# SchemaC-mcu.net
KiCad netlist of a schematic drawn in Altium Designer
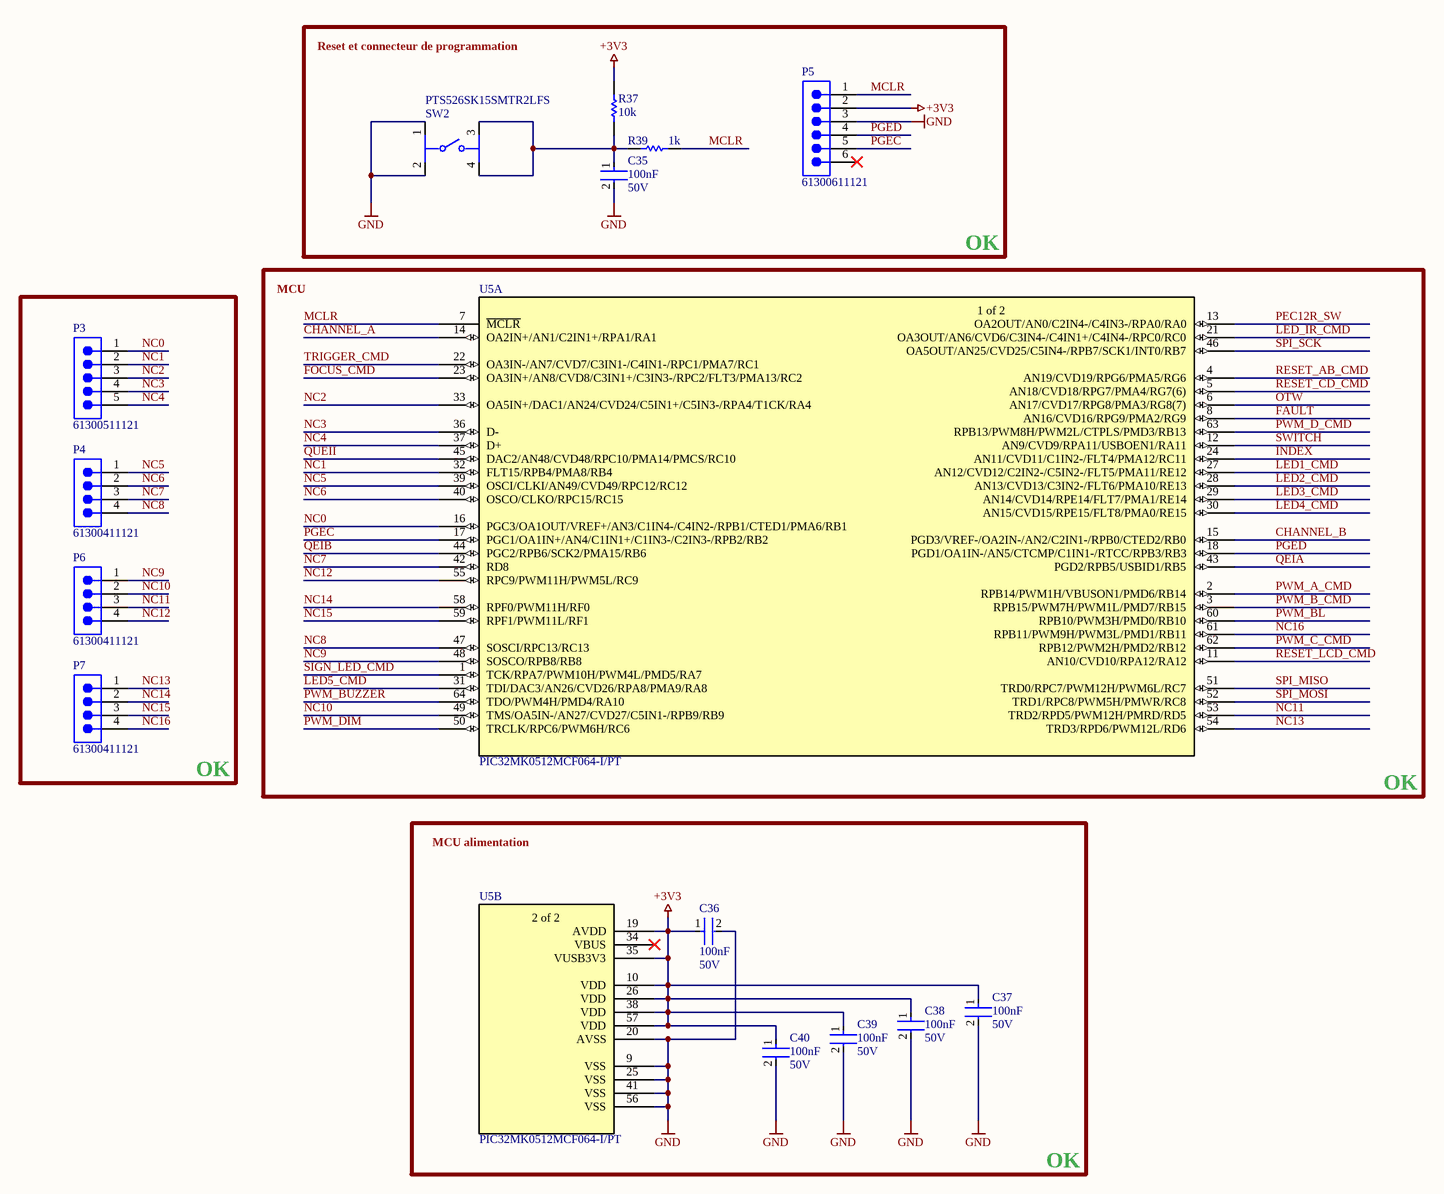
[diagram p0: SchemaC-mcu.SchDoc]

(export (version "E")
  (design (tool "Eeschema 10.0.6"))
  (components
    (comp (ref "C35")
      (value "CL21B104KBCNNNC")
      (footprint "FP-CL21-IPC_C")
      (description "CL21 Series 0805 100nF 50V ±10% Tolerance X7R Multilayer Ceramic Chip Capacitor")
      (fields
        (field (name "TOLERANCE") "10%")
        (field (name "CAPACITANCE") "100nF")
        (field (name "VOLTAGE RATING") "50V")
        (field (name "VOLTAGE") "50V")
      )
      (libsource (lib "Altium Content Vault") (part "b4654b650e69147ec39a6b967a45e02"))
    )
    (comp (ref "C36")
      (value "CL21B104KBCNNNC")
      (footprint "FP-CL21-IPC_C")
      (description "CL21 Series 0805 100nF 50V ±10% Tolerance X7R Multilayer Ceramic Chip Capacitor")
      (fields
        (field (name "TOLERANCE") "10%")
        (field (name "CAPACITANCE") "100nF")
        (field (name "VOLTAGE RATING") "50V")
        (field (name "VOLTAGE") "50V")
      )
      (libsource (lib "Altium Content Vault") (part "b4654b650e69147ec39a6b967a45e02"))
    )
    (comp (ref "C37")
      (value "CL21B104KBCNNNC")
      (footprint "FP-CL21-IPC_C")
      (description "CL21 Series 0805 100nF 50V ±10% Tolerance X7R Multilayer Ceramic Chip Capacitor")
      (fields
        (field (name "TOLERANCE") "10%")
        (field (name "CAPACITANCE") "100nF")
        (field (name "VOLTAGE RATING") "50V")
        (field (name "VOLTAGE") "50V")
      )
      (libsource (lib "Altium Content Vault") (part "b4654b650e69147ec39a6b967a45e02"))
    )
    (comp (ref "C38")
      (value "CL21B104KBCNNNC")
      (footprint "FP-CL21-IPC_C")
      (description "CL21 Series 0805 100nF 50V ±10% Tolerance X7R Multilayer Ceramic Chip Capacitor")
      (fields
        (field (name "TOLERANCE") "10%")
        (field (name "CAPACITANCE") "100nF")
        (field (name "VOLTAGE RATING") "50V")
        (field (name "VOLTAGE") "50V")
      )
      (libsource (lib "Altium Content Vault") (part "b4654b650e69147ec39a6b967a45e02"))
    )
    (comp (ref "C39")
      (value "CL21B104KBCNNNC")
      (footprint "FP-CL21-IPC_C")
      (description "CL21 Series 0805 100nF 50V ±10% Tolerance X7R Multilayer Ceramic Chip Capacitor")
      (fields
        (field (name "TOLERANCE") "10%")
        (field (name "CAPACITANCE") "100nF")
        (field (name "VOLTAGE RATING") "50V")
        (field (name "VOLTAGE") "50V")
      )
      (libsource (lib "Altium Content Vault") (part "b4654b650e69147ec39a6b967a45e02"))
    )
    (comp (ref "C40")
      (value "CL21B104KBCNNNC")
      (footprint "FP-CL21-IPC_C")
      (description "CL21 Series 0805 100nF 50V ±10% Tolerance X7R Multilayer Ceramic Chip Capacitor")
      (fields
        (field (name "TOLERANCE") "10%")
        (field (name "CAPACITANCE") "100nF")
        (field (name "VOLTAGE RATING") "50V")
        (field (name "VOLTAGE") "50V")
      )
      (libsource (lib "Altium Content Vault") (part "b4654b650e69147ec39a6b967a45e02"))
    )
    (comp (ref "P3")
      (value "61300511121")
      (footprint "61300511121")
      (libsource (lib "Altium Content Vault") (part "Header_Male_1R_05P"))
    )
    (comp (ref "P4")
      (value "61300411121")
      (footprint "61300411121")
      (libsource (lib "Altium Content Vault") (part "Header_Male_1R_04P"))
    )
    (comp (ref "P5")
      (value "61300611121")
      (footprint "61300611121")
      (libsource (lib "Altium Content Vault") (part "Header_Male_1R_06P"))
    )
    (comp (ref "P6")
      (value "61300411121")
      (footprint "61300411121")
      (libsource (lib "Altium Content Vault") (part "Header_Male_1R_04P"))
    )
    (comp (ref "P7")
      (value "61300411121")
      (footprint "61300411121")
      (libsource (lib "Altium Content Vault") (part "Header_Male_1R_04P"))
    )
    (comp (ref "R37")
      (value "RC0805JR-0710KL")
      (footprint "RESC2013X60X35ML10T20")
      (description "Chip Resistor, 10 KOhm, +/- 5%, 0.125 W, -55 to 155 degC, 0805 (2012 Metric), RoHS, Tape and Reel")
      (fields (field (name "MANUFACTURER") "Yageo") (field (name "RESISTANCE") "10k"))
      (libsource (lib "Altium Content Vault") (part "RES-2"))
    )
    (comp (ref "R39")
      (value "RC0805FR-071KL")
      (footprint "RESC2013X60X35ML10T20")
      (description "Chip Resistor, 1 KOhm, +/- 1%, 125 mW, -55 to 155 degC, 0805 (2012 Metric), RoHS, Tape and Reel")
      (fields
        (field (name "RESISTANCE") "1k")
        (field (name "TOLERANCE") "1%")
        (field (name "MANUFACTURER") "Yageo")
      )
      (libsource (lib "Altium Content Vault") (part "RES-2"))
    )
    (comp (ref "SW2")
      (value "PTS526SK15SMTR2LFS")
      (footprint "FP-PTS526SK15SMTR2LFS-MFG")
      (description "TACT 5.2 X 5.2, 1.5 MM H, 260GF,")
      (fields
        (field (name "MANUFACTURER") "C&K")
        (field (name "OCTOPART") "https://octopart.com/pts526+sk15+smtr2+lfs-c%26k+components-100617999")
      )
      (libsource (lib "Altium Content Vault") (part "b8895f3f4cefb76e1819d2863dba89b"))
    )
    (comp (ref "U5")
      (value "PIC32MK0512MCF064-I/PT")
      (footprint "TQFP64_PT_MCH")
      (fields (field (name "COPYRIGHT") "Copyright (C) 2023 Ultra Librarian. All rights reserved."))
      (libsource (lib "SymbLib") (part "PIC32MK0512MCF064-I/PT"))
    )
  )
  (nets
    (net (code "1") (name "+3V3") (class "Default")
      (node (ref "C36") (pin "1") (pinfunction "1_1") (pintype "passive"))
      (node (ref "C37") (pin "1") (pinfunction "1_1") (pintype "passive"))
      (node (ref "C38") (pin "1") (pinfunction "1_1") (pintype "passive"))
      (node (ref "C39") (pin "1") (pinfunction "1_1") (pintype "passive"))
      (node (ref "C40") (pin "1") (pinfunction "1_1") (pintype "passive"))
      (node (ref "P5") (pin "2") (pinfunction "2_2") (pintype "passive"))
      (node (ref "R37") (pin "1") (pinfunction "1_1") (pintype "passive"))
      (node (ref "U5") (pin "10") (pinfunction "VDD_10") (pintype "power_in"))
      (node (ref "U5") (pin "19") (pinfunction "AVDD_19") (pintype "power_in"))
      (node (ref "U5") (pin "26") (pinfunction "VDD_26") (pintype "power_in"))
      (node (ref "U5") (pin "35") (pinfunction "VUSB3V3_35") (pintype "power_in"))
      (node (ref "U5") (pin "38") (pinfunction "VDD_38") (pintype "power_in"))
      (node (ref "U5") (pin "57") (pinfunction "VDD_57") (pintype "power_in"))
    )
    (net (code "2") (name "/CHANNEL_A") (class "Default")
      (node (ref "U5") (pin "14") (pinfunction "OA2IN+/AN1/C2IN1+/RPA1/RA1_14") (pintype "bidirectional"))
    )
    (net (code "3") (name "/CHANNEL_B") (class "Default")
      (node (ref "U5") (pin "15") (pinfunction "PGD3/VREF-/OA2IN-/AN2/C2IN1-/RPB0/CTED2/RB0_15") (pintype "bidirectional"))
    )
    (net (code "4") (name "/FAULT") (class "Default")
      (node (ref "U5") (pin "8") (pinfunction "AN16/CVD16/RPG9/PMA2/RG9_8") (pintype "bidirectional"))
    )
    (net (code "5") (name "/FOCUS_CMD") (class "Default")
      (node (ref "U5") (pin "23") (pinfunction "OA3IN+/AN8/CVD8/C3IN1+/C3IN3-/RPC2/FLT3/PMA13/RC2_23") (pintype "bidirectional"))
    )
    (net (code "6") (name "/INDEX") (class "Default")
      (node (ref "U5") (pin "24") (pinfunction "AN11/CVD11/C1IN2-/FLT4/PMA12/RC11_24") (pintype "bidirectional"))
    )
    (net (code "7") (name "/LED1_CMD") (class "Default")
      (node (ref "U5") (pin "27") (pinfunction "AN12/CVD12/C2IN2-/C5IN2-/FLT5/PMA11/RE12_27") (pintype "bidirectional"))
    )
    (net (code "8") (name "/LED2_CMD") (class "Default")
      (node (ref "U5") (pin "28") (pinfunction "AN13/CVD13/C3IN2-/FLT6/PMA10/RE13_28") (pintype "bidirectional"))
    )
    (net (code "9") (name "/LED3_CMD") (class "Default")
      (node (ref "U5") (pin "29") (pinfunction "AN14/CVD14/RPE14/FLT7/PMA1/RE14_29") (pintype "bidirectional"))
    )
    (net (code "10") (name "/LED4_CMD") (class "Default")
      (node (ref "U5") (pin "30") (pinfunction "AN15/CVD15/RPE15/FLT8/PMA0/RE15_30") (pintype "bidirectional"))
    )
    (net (code "11") (name "/LED5_CMD") (class "Default")
      (node (ref "U5") (pin "31") (pinfunction "TDI/DAC3/AN26/CVD26/RPA8/PMA9/RA8_31") (pintype "bidirectional"))
    )
    (net (code "12") (name "/LED_IR_CMD") (class "Default")
      (node (ref "U5") (pin "21") (pinfunction "OA3OUT/AN6/CVD6/C3IN4-/C4IN1+/C4IN4-/RPC0/RC0_21") (pintype "bidirectional"))
    )
    (net (code "13") (name "/MCLR") (class "Default")
      (node (ref "P5") (pin "1") (pinfunction "1_1") (pintype "passive"))
      (node (ref "R39") (pin "2") (pinfunction "2_2") (pintype "passive"))
      (node (ref "U5") (pin "7") (pinfunction "~{MCLR}_7") (pintype "passive"))
    )
    (net (code "14") (name "/NC0") (class "Default")
      (node (ref "P3") (pin "1") (pinfunction "1_1") (pintype "passive"))
      (node (ref "U5") (pin "16") (pinfunction "PGC3/OA1OUT/VREF+/AN3/C1IN4-/C4IN2-/RPB1/CTED1/PMA6/RB1_16") (pintype "bidirectional"))
    )
    (net (code "15") (name "/NC1") (class "Default")
      (node (ref "P3") (pin "2") (pinfunction "2_2") (pintype "passive"))
      (node (ref "U5") (pin "32") (pinfunction "FLT15/RPB4/PMA8/RB4_32") (pintype "bidirectional"))
    )
    (net (code "16") (name "/NC2") (class "Default")
      (node (ref "P3") (pin "3") (pinfunction "3_3") (pintype "passive"))
      (node (ref "U5") (pin "33") (pinfunction "OA5IN+/DAC1/AN24/CVD24/C5IN1+/C5IN3-/RPA4/T1CK/RA4_33") (pintype "bidirectional"))
    )
    (net (code "17") (name "/NC3") (class "Default")
      (node (ref "P3") (pin "4") (pinfunction "4_4") (pintype "passive"))
      (node (ref "U5") (pin "36") (pinfunction "D-_36") (pintype "bidirectional"))
    )
    (net (code "18") (name "/NC4") (class "Default")
      (node (ref "P3") (pin "5") (pinfunction "5_5") (pintype "passive"))
      (node (ref "U5") (pin "37") (pinfunction "D+_37") (pintype "bidirectional"))
    )
    (net (code "19") (name "/NC5") (class "Default")
      (node (ref "P4") (pin "1") (pinfunction "1_1") (pintype "passive"))
      (node (ref "U5") (pin "39") (pinfunction "OSCI/CLKI/AN49/CVD49/RPC12/RC12_39") (pintype "bidirectional"))
    )
    (net (code "20") (name "/NC6") (class "Default")
      (node (ref "P4") (pin "2") (pinfunction "2_2") (pintype "passive"))
      (node (ref "U5") (pin "40") (pinfunction "OSCO/CLKO/RPC15/RC15_40") (pintype "bidirectional"))
    )
    (net (code "21") (name "/NC7") (class "Default")
      (node (ref "P4") (pin "3") (pinfunction "3_3") (pintype "passive"))
      (node (ref "U5") (pin "42") (pinfunction "RD8_42") (pintype "bidirectional"))
    )
    (net (code "22") (name "/NC8") (class "Default")
      (node (ref "P4") (pin "4") (pinfunction "4_4") (pintype "passive"))
      (node (ref "U5") (pin "47") (pinfunction "SOSCI/RPC13/RC13_47") (pintype "bidirectional"))
    )
    (net (code "23") (name "/NC9") (class "Default")
      (node (ref "P6") (pin "1") (pinfunction "1_1") (pintype "passive"))
      (node (ref "U5") (pin "48") (pinfunction "SOSCO/RPB8/RB8_48") (pintype "bidirectional"))
    )
    (net (code "24") (name "/NC10") (class "Default")
      (node (ref "P6") (pin "2") (pinfunction "2_2") (pintype "passive"))
      (node (ref "U5") (pin "49") (pinfunction "TMS/OA5IN-/AN27/CVD27/C5IN1-/RPB9/RB9_49") (pintype "bidirectional"))
    )
    (net (code "25") (name "/NC11") (class "Default")
      (node (ref "P6") (pin "3") (pinfunction "3_3") (pintype "passive"))
      (node (ref "U5") (pin "53") (pinfunction "TRD2/RPD5/PWM12H/PMRD/RD5_53") (pintype "bidirectional"))
    )
    (net (code "26") (name "/NC12") (class "Default")
      (node (ref "P6") (pin "4") (pinfunction "4_4") (pintype "passive"))
      (node (ref "U5") (pin "55") (pinfunction "RPC9/PWM11H/PWM5L/RC9_55") (pintype "bidirectional"))
    )
    (net (code "27") (name "/NC13") (class "Default")
      (node (ref "P7") (pin "1") (pinfunction "1_1") (pintype "passive"))
      (node (ref "U5") (pin "54") (pinfunction "TRD3/RPD6/PWM12L/RD6_54") (pintype "bidirectional"))
    )
    (net (code "28") (name "/NC14") (class "Default")
      (node (ref "P7") (pin "2") (pinfunction "2_2") (pintype "passive"))
      (node (ref "U5") (pin "58") (pinfunction "RPF0/PWM11H/RF0_58") (pintype "bidirectional"))
    )
    (net (code "29") (name "/NC15") (class "Default")
      (node (ref "P7") (pin "3") (pinfunction "3_3") (pintype "passive"))
      (node (ref "U5") (pin "59") (pinfunction "RPF1/PWM11L/RF1_59") (pintype "bidirectional"))
    )
    (net (code "30") (name "/NC16") (class "Default")
      (node (ref "P7") (pin "4") (pinfunction "4_4") (pintype "passive"))
      (node (ref "U5") (pin "61") (pinfunction "RPB11/PWM9H/PWM3L/PMD1/RB11_61") (pintype "bidirectional"))
    )
    (net (code "31") (name "/OTW") (class "Default")
      (node (ref "U5") (pin "6") (pinfunction "AN17/CVD17/RPG8/PMA3/RG8(7)_6") (pintype "bidirectional"))
    )
    (net (code "32") (name "/PEC12R_SW") (class "Default")
      (node (ref "U5") (pin "13") (pinfunction "OA2OUT/AN0/C2IN4-/C4IN3-/RPA0/RA0_13") (pintype "bidirectional"))
    )
    (net (code "33") (name "/PGEC") (class "Default")
      (node (ref "P5") (pin "5") (pinfunction "5_5") (pintype "passive"))
      (node (ref "U5") (pin "17") (pinfunction "PGC1/OA1IN+/AN4/C1IN1+/C1IN3-/C2IN3-/RPB2/RB2_17") (pintype "bidirectional"))
    )
    (net (code "34") (name "/PGED") (class "Default")
      (node (ref "P5") (pin "4") (pinfunction "4_4") (pintype "passive"))
      (node (ref "U5") (pin "18") (pinfunction "PGD1/OA1IN-/AN5/CTCMP/C1IN1-/RTCC/RPB3/RB3_18") (pintype "bidirectional"))
    )
    (net (code "35") (name "/PWM_A_CMD") (class "Default")
      (node (ref "U5") (pin "2") (pinfunction "RPB14/PWM1H/VBUSON1/PMD6/RB14_2") (pintype "bidirectional"))
    )
    (net (code "36") (name "/PWM_BL") (class "Default")
      (node (ref "U5") (pin "60") (pinfunction "RPB10/PWM3H/PMD0/RB10_60") (pintype "bidirectional"))
    )
    (net (code "37") (name "/PWM_BUZZER") (class "Default")
      (node (ref "U5") (pin "64") (pinfunction "TDO/PWM4H/PMD4/RA10_64") (pintype "bidirectional"))
    )
    (net (code "38") (name "/PWM_B_CMD") (class "Default")
      (node (ref "U5") (pin "3") (pinfunction "RPB15/PWM7H/PWM1L/PMD7/RB15_3") (pintype "bidirectional"))
    )
    (net (code "39") (name "/PWM_C_CMD") (class "Default")
      (node (ref "U5") (pin "62") (pinfunction "RPB12/PWM2H/PMD2/RB12_62") (pintype "bidirectional"))
    )
    (net (code "40") (name "/PWM_DIM") (class "Default")
      (node (ref "U5") (pin "50") (pinfunction "TRCLK/RPC6/PWM6H/RC6_50") (pintype "bidirectional"))
    )
    (net (code "41") (name "/PWM_D_CMD") (class "Default")
      (node (ref "U5") (pin "63") (pinfunction "RPB13/PWM8H/PWM2L/CTPLS/PMD3/RB13_63") (pintype "bidirectional"))
    )
    (net (code "42") (name "/QEIA") (class "Default")
      (node (ref "U5") (pin "43") (pinfunction "PGD2/RPB5/USBID1/RB5_43") (pintype "bidirectional"))
    )
    (net (code "43") (name "/QEIB") (class "Default")
      (node (ref "U5") (pin "44") (pinfunction "PGC2/RPB6/SCK2/PMA15/RB6_44") (pintype "bidirectional"))
    )
    (net (code "44") (name "/QUEII") (class "Default")
      (node (ref "U5") (pin "45") (pinfunction "DAC2/AN48/CVD48/RPC10/PMA14/PMCS/RC10_45") (pintype "bidirectional"))
    )
    (net (code "45") (name "/RESET_AB_CMD") (class "Default")
      (node (ref "U5") (pin "4") (pinfunction "AN19/CVD19/RPG6/PMA5/RG6_4") (pintype "bidirectional"))
    )
    (net (code "46") (name "/RESET_CD_CMD") (class "Default")
      (node (ref "U5") (pin "5") (pinfunction "AN18/CVD18/RPG7/PMA4/RG7(6)_5") (pintype "bidirectional"))
    )
    (net (code "47") (name "/RESET_LCD_CMD") (class "Default")
      (node (ref "U5") (pin "11") (pinfunction "AN10/CVD10/RPA12/RA12_11") (pintype "bidirectional"))
    )
    (net (code "48") (name "/SIGN_LED_CMD") (class "Default")
      (node (ref "U5") (pin "1") (pinfunction "TCK/RPA7/PWM10H/PWM4L/PMD5/RA7_1") (pintype "bidirectional"))
    )
    (net (code "49") (name "/SPI_MISO") (class "Default")
      (node (ref "U5") (pin "51") (pinfunction "TRD0/RPC7/PWM12H/PWM6L/RC7_51") (pintype "bidirectional"))
    )
    (net (code "50") (name "/SPI_MOSI") (class "Default")
      (node (ref "U5") (pin "52") (pinfunction "TRD1/RPC8/PWM5H/PMWR/RC8_52") (pintype "bidirectional"))
    )
    (net (code "51") (name "/SPI_SCK") (class "Default")
      (node (ref "U5") (pin "46") (pinfunction "OA5OUT/AN25/CVD25/C5IN4-/RPB7/SCK1/INT0/RB7_46") (pintype "bidirectional"))
    )
    (net (code "52") (name "/SWITCH") (class "Default")
      (node (ref "U5") (pin "12") (pinfunction "AN9/CVD9/RPA11/USBOEN1/RA11_12") (pintype "bidirectional"))
    )
    (net (code "53") (name "/TRIGGER_CMD") (class "Default")
      (node (ref "U5") (pin "22") (pinfunction "OA3IN-/AN7/CVD7/C3IN1-/C4IN1-/RPC1/PMA7/RC1_22") (pintype "bidirectional"))
    )
    (net (code "54") (name "GND") (class "Default")
      (node (ref "C35") (pin "2") (pinfunction "2_2") (pintype "passive"))
      (node (ref "C36") (pin "2") (pinfunction "2_2") (pintype "passive"))
      (node (ref "C37") (pin "2") (pinfunction "2_2") (pintype "passive"))
      (node (ref "C38") (pin "2") (pinfunction "2_2") (pintype "passive"))
      (node (ref "C39") (pin "2") (pinfunction "2_2") (pintype "passive"))
      (node (ref "C40") (pin "2") (pinfunction "2_2") (pintype "passive"))
      (node (ref "P5") (pin "3") (pinfunction "3_3") (pintype "passive"))
      (node (ref "SW2") (pin "1") (pinfunction "1_1") (pintype "passive"))
      (node (ref "SW2") (pin "2") (pinfunction "2_2") (pintype "passive"))
      (node (ref "U5") (pin "20") (pinfunction "AVSS_20") (pintype "passive"))
      (node (ref "U5") (pin "25") (pinfunction "VSS_25") (pintype "passive"))
      (node (ref "U5") (pin "41") (pinfunction "VSS_41") (pintype "passive"))
      (node (ref "U5") (pin "56") (pinfunction "VSS_56") (pintype "passive"))
      (node (ref "U5") (pin "9") (pinfunction "VSS_9") (pintype "passive"))
    )
    (net (code "55") (name "Net-(C35-Pad1)") (class "Default")
      (node (ref "C35") (pin "1") (pinfunction "1_1") (pintype "passive"))
      (node (ref "R37") (pin "2") (pinfunction "2_2") (pintype "passive"))
      (node (ref "R39") (pin "1") (pinfunction "1_1") (pintype "passive"))
      (node (ref "SW2") (pin "3") (pinfunction "3_3") (pintype "passive"))
      (node (ref "SW2") (pin "4") (pinfunction "4_4") (pintype "passive"))
    )
    (net (code "56") (name "unconnected-(P5-Pad6)") (class "Default")
      (node (ref "P5") (pin "6") (pinfunction "6_6") (pintype "passive+no_connect"))
    )
    (net (code "57") (name "unconnected-(U5B-VBUS-Pad34)") (class "Default")
      (node (ref "U5") (pin "34") (pinfunction "VBUS_34") (pintype "power_in+no_connect"))
    )
  )
)
